# Tranducer_Channel.net
KiCad netlist of a schematic drawn in Altium Designer
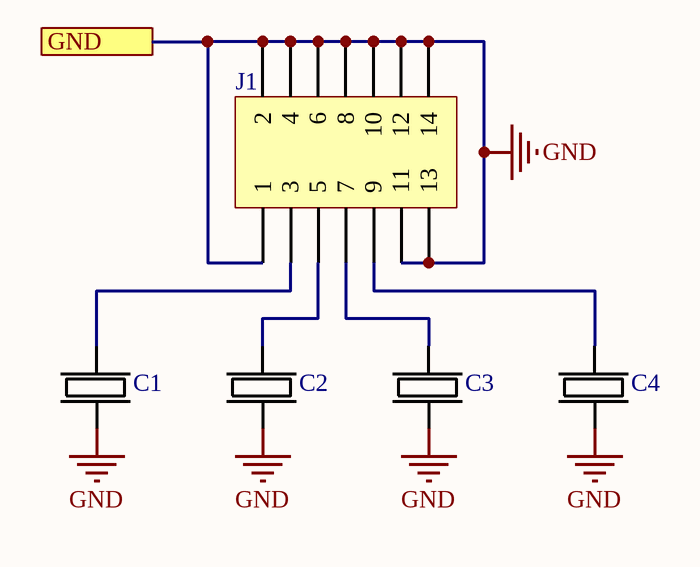
[diagram p0: Tranducer_Channel.SchDoc]

(export (version "E")
  (design (tool "Eeschema 10.0.6"))
  (components
    (comp (ref "C1")
      (value "Transducer")
      (footprint "Transducer")
      (libsource (lib "Transducer") (part "Transducer"))
    )
    (comp (ref "C2")
      (value "Transducer")
      (footprint "Transducer")
      (libsource (lib "Transducer") (part "Transducer"))
    )
    (comp (ref "C3")
      (value "Transducer")
      (footprint "Transducer")
      (libsource (lib "Transducer") (part "Transducer"))
    )
    (comp (ref "C4")
      (value "Transducer")
      (footprint "Transducer")
      (libsource (lib "Transducer") (part "Transducer"))
    )
    (comp (ref "J1")
      (value "Header 7X2")
      (footprint "CONN_14x2_0.5IN")
      (description "Header, 7-Pin, Dual row")
      (fields (field (name "PUBLISHER") "Altium Limited"))
      (libsource (lib "Miscellaneous Connectors") (part "Header 7X2"))
    )
  )
  (nets
    (net (code "1") (name "GND") (class "Default")
      (node (ref "C1") (pin "2") (pintype "passive"))
      (node (ref "C2") (pin "2") (pintype "passive"))
      (node (ref "C3") (pin "2") (pintype "passive"))
      (node (ref "C4") (pin "2") (pintype "passive"))
      (node (ref "J1") (pin "1") (pinfunction "1_1") (pintype "passive"))
      (node (ref "J1") (pin "10") (pinfunction "10_10") (pintype "passive"))
      (node (ref "J1") (pin "11") (pinfunction "11_11") (pintype "passive"))
      (node (ref "J1") (pin "12") (pinfunction "12_12") (pintype "passive"))
      (node (ref "J1") (pin "13") (pinfunction "13_13") (pintype "passive"))
      (node (ref "J1") (pin "14") (pinfunction "14_14") (pintype "passive"))
      (node (ref "J1") (pin "2") (pinfunction "2_2") (pintype "passive"))
      (node (ref "J1") (pin "4") (pinfunction "4_4") (pintype "passive"))
      (node (ref "J1") (pin "6") (pinfunction "6_6") (pintype "passive"))
      (node (ref "J1") (pin "8") (pinfunction "8_8") (pintype "passive"))
    )
    (net (code "2") (name "Net-(C1-Pad1)") (class "Default")
      (node (ref "C1") (pin "1") (pintype "passive"))
      (node (ref "J1") (pin "3") (pinfunction "3_3") (pintype "passive"))
    )
    (net (code "3") (name "Net-(C2-Pad1)") (class "Default")
      (node (ref "C2") (pin "1") (pintype "passive"))
      (node (ref "J1") (pin "5") (pinfunction "5_5") (pintype "passive"))
    )
    (net (code "4") (name "Net-(C3-Pad1)") (class "Default")
      (node (ref "C3") (pin "1") (pintype "passive"))
      (node (ref "J1") (pin "7") (pinfunction "7_7") (pintype "passive"))
    )
    (net (code "5") (name "Net-(C4-Pad1)") (class "Default")
      (node (ref "C4") (pin "1") (pintype "passive"))
      (node (ref "J1") (pin "9") (pinfunction "9_9") (pintype "passive"))
    )
  )
)
